# switch_input.net
KiCad netlist of a schematic drawn in Altium Designer
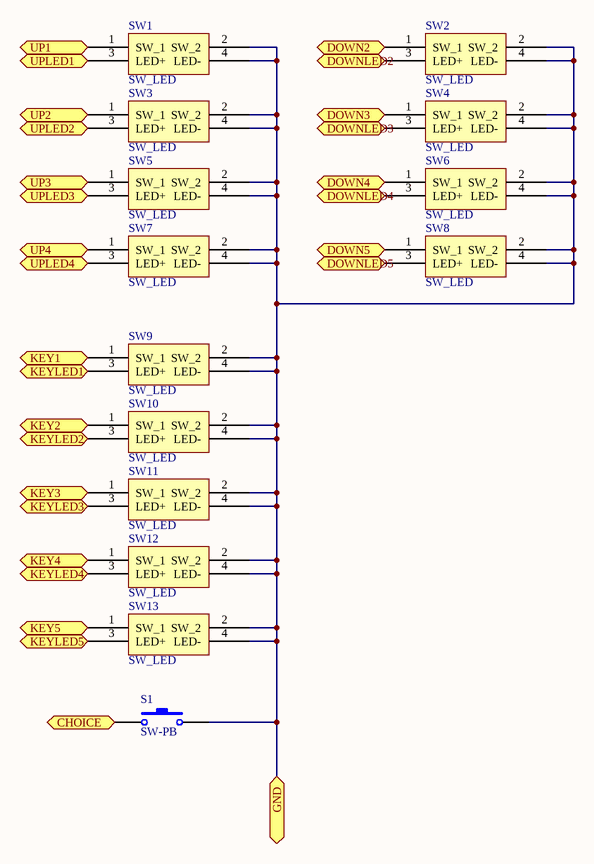
[diagram p0: switch_input.SchDoc]

(export (version "E")
  (design (tool "Eeschema 10.0.6"))
  (components
    (comp (ref "S1")
      (value "SW-PB")
      (footprint "SW2")
      (description "Switch")
      (fields (field (name "PUBLISHER") "Altium Limited"))
      (libsource (lib "Miscellaneous Devices") (part "SW-PB"))
    )
    (comp (ref "SW1") (value "SW_LED") (footprint "SW_LED") (libsource (lib "mylib") (part "SW_LED")))
    (comp (ref "SW2") (value "SW_LED") (footprint "SW_LED") (libsource (lib "mylib") (part "SW_LED")))
    (comp (ref "SW3") (value "SW_LED") (footprint "SW_LED") (libsource (lib "mylib") (part "SW_LED")))
    (comp (ref "SW4") (value "SW_LED") (footprint "SW_LED") (libsource (lib "mylib") (part "SW_LED")))
    (comp (ref "SW5") (value "SW_LED") (footprint "SW_LED") (libsource (lib "mylib") (part "SW_LED")))
    (comp (ref "SW6") (value "SW_LED") (footprint "SW_LED") (libsource (lib "mylib") (part "SW_LED")))
    (comp (ref "SW7") (value "SW_LED") (footprint "SW_LED") (libsource (lib "mylib") (part "SW_LED")))
    (comp (ref "SW8") (value "SW_LED") (footprint "SW_LED") (libsource (lib "mylib") (part "SW_LED")))
    (comp (ref "SW9") (value "SW_LED") (footprint "SW_LED") (libsource (lib "mylib") (part "SW_LED")))
    (comp (ref "SW10") (value "SW_LED") (footprint "SW_LED") (libsource (lib "mylib") (part "SW_LED")))
    (comp (ref "SW11") (value "SW_LED") (footprint "SW_LED") (libsource (lib "mylib") (part "SW_LED")))
    (comp (ref "SW12") (value "SW_LED") (footprint "SW_LED") (libsource (lib "mylib") (part "SW_LED")))
    (comp (ref "SW13") (value "SW_LED") (footprint "SW_LED") (libsource (lib "mylib") (part "SW_LED")))
  )
  (nets
    (net (code "1") (name "/CHOICE") (class "Default")
      (node (ref "S1") (pin "1") (pinfunction "1_1") (pintype "passive"))
    )
    (net (code "2") (name "/DOWN2") (class "Default")
      (node (ref "SW2") (pin "1") (pinfunction "SW_1_1") (pintype "passive"))
    )
    (net (code "3") (name "/DOWN3") (class "Default")
      (node (ref "SW4") (pin "1") (pinfunction "SW_1_1") (pintype "passive"))
    )
    (net (code "4") (name "/DOWN4") (class "Default")
      (node (ref "SW6") (pin "1") (pinfunction "SW_1_1") (pintype "passive"))
    )
    (net (code "5") (name "/DOWN5") (class "Default")
      (node (ref "SW8") (pin "1") (pinfunction "SW_1_1") (pintype "passive"))
    )
    (net (code "6") (name "/DOWNLED2") (class "Default")
      (node (ref "SW2") (pin "3") (pinfunction "LED+_3") (pintype "passive"))
    )
    (net (code "7") (name "/DOWNLED3") (class "Default")
      (node (ref "SW4") (pin "3") (pinfunction "LED+_3") (pintype "passive"))
    )
    (net (code "8") (name "/DOWNLED4") (class "Default")
      (node (ref "SW6") (pin "3") (pinfunction "LED+_3") (pintype "passive"))
    )
    (net (code "9") (name "/DOWNLED5") (class "Default")
      (node (ref "SW8") (pin "3") (pinfunction "LED+_3") (pintype "passive"))
    )
    (net (code "10") (name "/GND") (class "Default")
      (node (ref "S1") (pin "2") (pinfunction "2_2") (pintype "passive"))
      (node (ref "SW1") (pin "2") (pinfunction "SW_2_2") (pintype "passive"))
      (node (ref "SW1") (pin "4") (pinfunction "LED-_4") (pintype "passive"))
      (node (ref "SW10") (pin "2") (pinfunction "SW_2_2") (pintype "passive"))
      (node (ref "SW10") (pin "4") (pinfunction "LED-_4") (pintype "passive"))
      (node (ref "SW11") (pin "2") (pinfunction "SW_2_2") (pintype "passive"))
      (node (ref "SW11") (pin "4") (pinfunction "LED-_4") (pintype "passive"))
      (node (ref "SW12") (pin "2") (pinfunction "SW_2_2") (pintype "passive"))
      (node (ref "SW12") (pin "4") (pinfunction "LED-_4") (pintype "passive"))
      (node (ref "SW13") (pin "2") (pinfunction "SW_2_2") (pintype "passive"))
      (node (ref "SW13") (pin "4") (pinfunction "LED-_4") (pintype "passive"))
      (node (ref "SW2") (pin "2") (pinfunction "SW_2_2") (pintype "passive"))
      (node (ref "SW2") (pin "4") (pinfunction "LED-_4") (pintype "passive"))
      (node (ref "SW3") (pin "2") (pinfunction "SW_2_2") (pintype "passive"))
      (node (ref "SW3") (pin "4") (pinfunction "LED-_4") (pintype "passive"))
      (node (ref "SW4") (pin "2") (pinfunction "SW_2_2") (pintype "passive"))
      (node (ref "SW4") (pin "4") (pinfunction "LED-_4") (pintype "passive"))
      (node (ref "SW5") (pin "2") (pinfunction "SW_2_2") (pintype "passive"))
      (node (ref "SW5") (pin "4") (pinfunction "LED-_4") (pintype "passive"))
      (node (ref "SW6") (pin "2") (pinfunction "SW_2_2") (pintype "passive"))
      (node (ref "SW6") (pin "4") (pinfunction "LED-_4") (pintype "passive"))
      (node (ref "SW7") (pin "2") (pinfunction "SW_2_2") (pintype "passive"))
      (node (ref "SW7") (pin "4") (pinfunction "LED-_4") (pintype "passive"))
      (node (ref "SW8") (pin "2") (pinfunction "SW_2_2") (pintype "passive"))
      (node (ref "SW8") (pin "4") (pinfunction "LED-_4") (pintype "passive"))
      (node (ref "SW9") (pin "2") (pinfunction "SW_2_2") (pintype "passive"))
      (node (ref "SW9") (pin "4") (pinfunction "LED-_4") (pintype "passive"))
    )
    (net (code "11") (name "/KEY1") (class "Default")
      (node (ref "SW9") (pin "1") (pinfunction "SW_1_1") (pintype "passive"))
    )
    (net (code "12") (name "/KEY2") (class "Default")
      (node (ref "SW10") (pin "1") (pinfunction "SW_1_1") (pintype "passive"))
    )
    (net (code "13") (name "/KEY3") (class "Default")
      (node (ref "SW11") (pin "1") (pinfunction "SW_1_1") (pintype "passive"))
    )
    (net (code "14") (name "/KEY4") (class "Default")
      (node (ref "SW12") (pin "1") (pinfunction "SW_1_1") (pintype "passive"))
    )
    (net (code "15") (name "/KEY5") (class "Default")
      (node (ref "SW13") (pin "1") (pinfunction "SW_1_1") (pintype "passive"))
    )
    (net (code "16") (name "/KEYLED1") (class "Default")
      (node (ref "SW9") (pin "3") (pinfunction "LED+_3") (pintype "passive"))
    )
    (net (code "17") (name "/KEYLED2") (class "Default")
      (node (ref "SW10") (pin "3") (pinfunction "LED+_3") (pintype "passive"))
    )
    (net (code "18") (name "/KEYLED3") (class "Default")
      (node (ref "SW11") (pin "3") (pinfunction "LED+_3") (pintype "passive"))
    )
    (net (code "19") (name "/KEYLED4") (class "Default")
      (node (ref "SW12") (pin "3") (pinfunction "LED+_3") (pintype "passive"))
    )
    (net (code "20") (name "/KEYLED5") (class "Default")
      (node (ref "SW13") (pin "3") (pinfunction "LED+_3") (pintype "passive"))
    )
    (net (code "21") (name "/UP1") (class "Default")
      (node (ref "SW1") (pin "1") (pinfunction "SW_1_1") (pintype "passive"))
    )
    (net (code "22") (name "/UP2") (class "Default")
      (node (ref "SW3") (pin "1") (pinfunction "SW_1_1") (pintype "passive"))
    )
    (net (code "23") (name "/UP3") (class "Default")
      (node (ref "SW5") (pin "1") (pinfunction "SW_1_1") (pintype "passive"))
    )
    (net (code "24") (name "/UP4") (class "Default")
      (node (ref "SW7") (pin "1") (pinfunction "SW_1_1") (pintype "passive"))
    )
    (net (code "25") (name "/UPLED1") (class "Default")
      (node (ref "SW1") (pin "3") (pinfunction "LED+_3") (pintype "passive"))
    )
    (net (code "26") (name "/UPLED2") (class "Default")
      (node (ref "SW3") (pin "3") (pinfunction "LED+_3") (pintype "passive"))
    )
    (net (code "27") (name "/UPLED3") (class "Default")
      (node (ref "SW5") (pin "3") (pinfunction "LED+_3") (pintype "passive"))
    )
    (net (code "28") (name "/UPLED4") (class "Default")
      (node (ref "SW7") (pin "3") (pinfunction "LED+_3") (pintype "passive"))
    )
  )
)
